# USB_To_TTL.net
KiCad netlist of a schematic drawn in Altium Designer
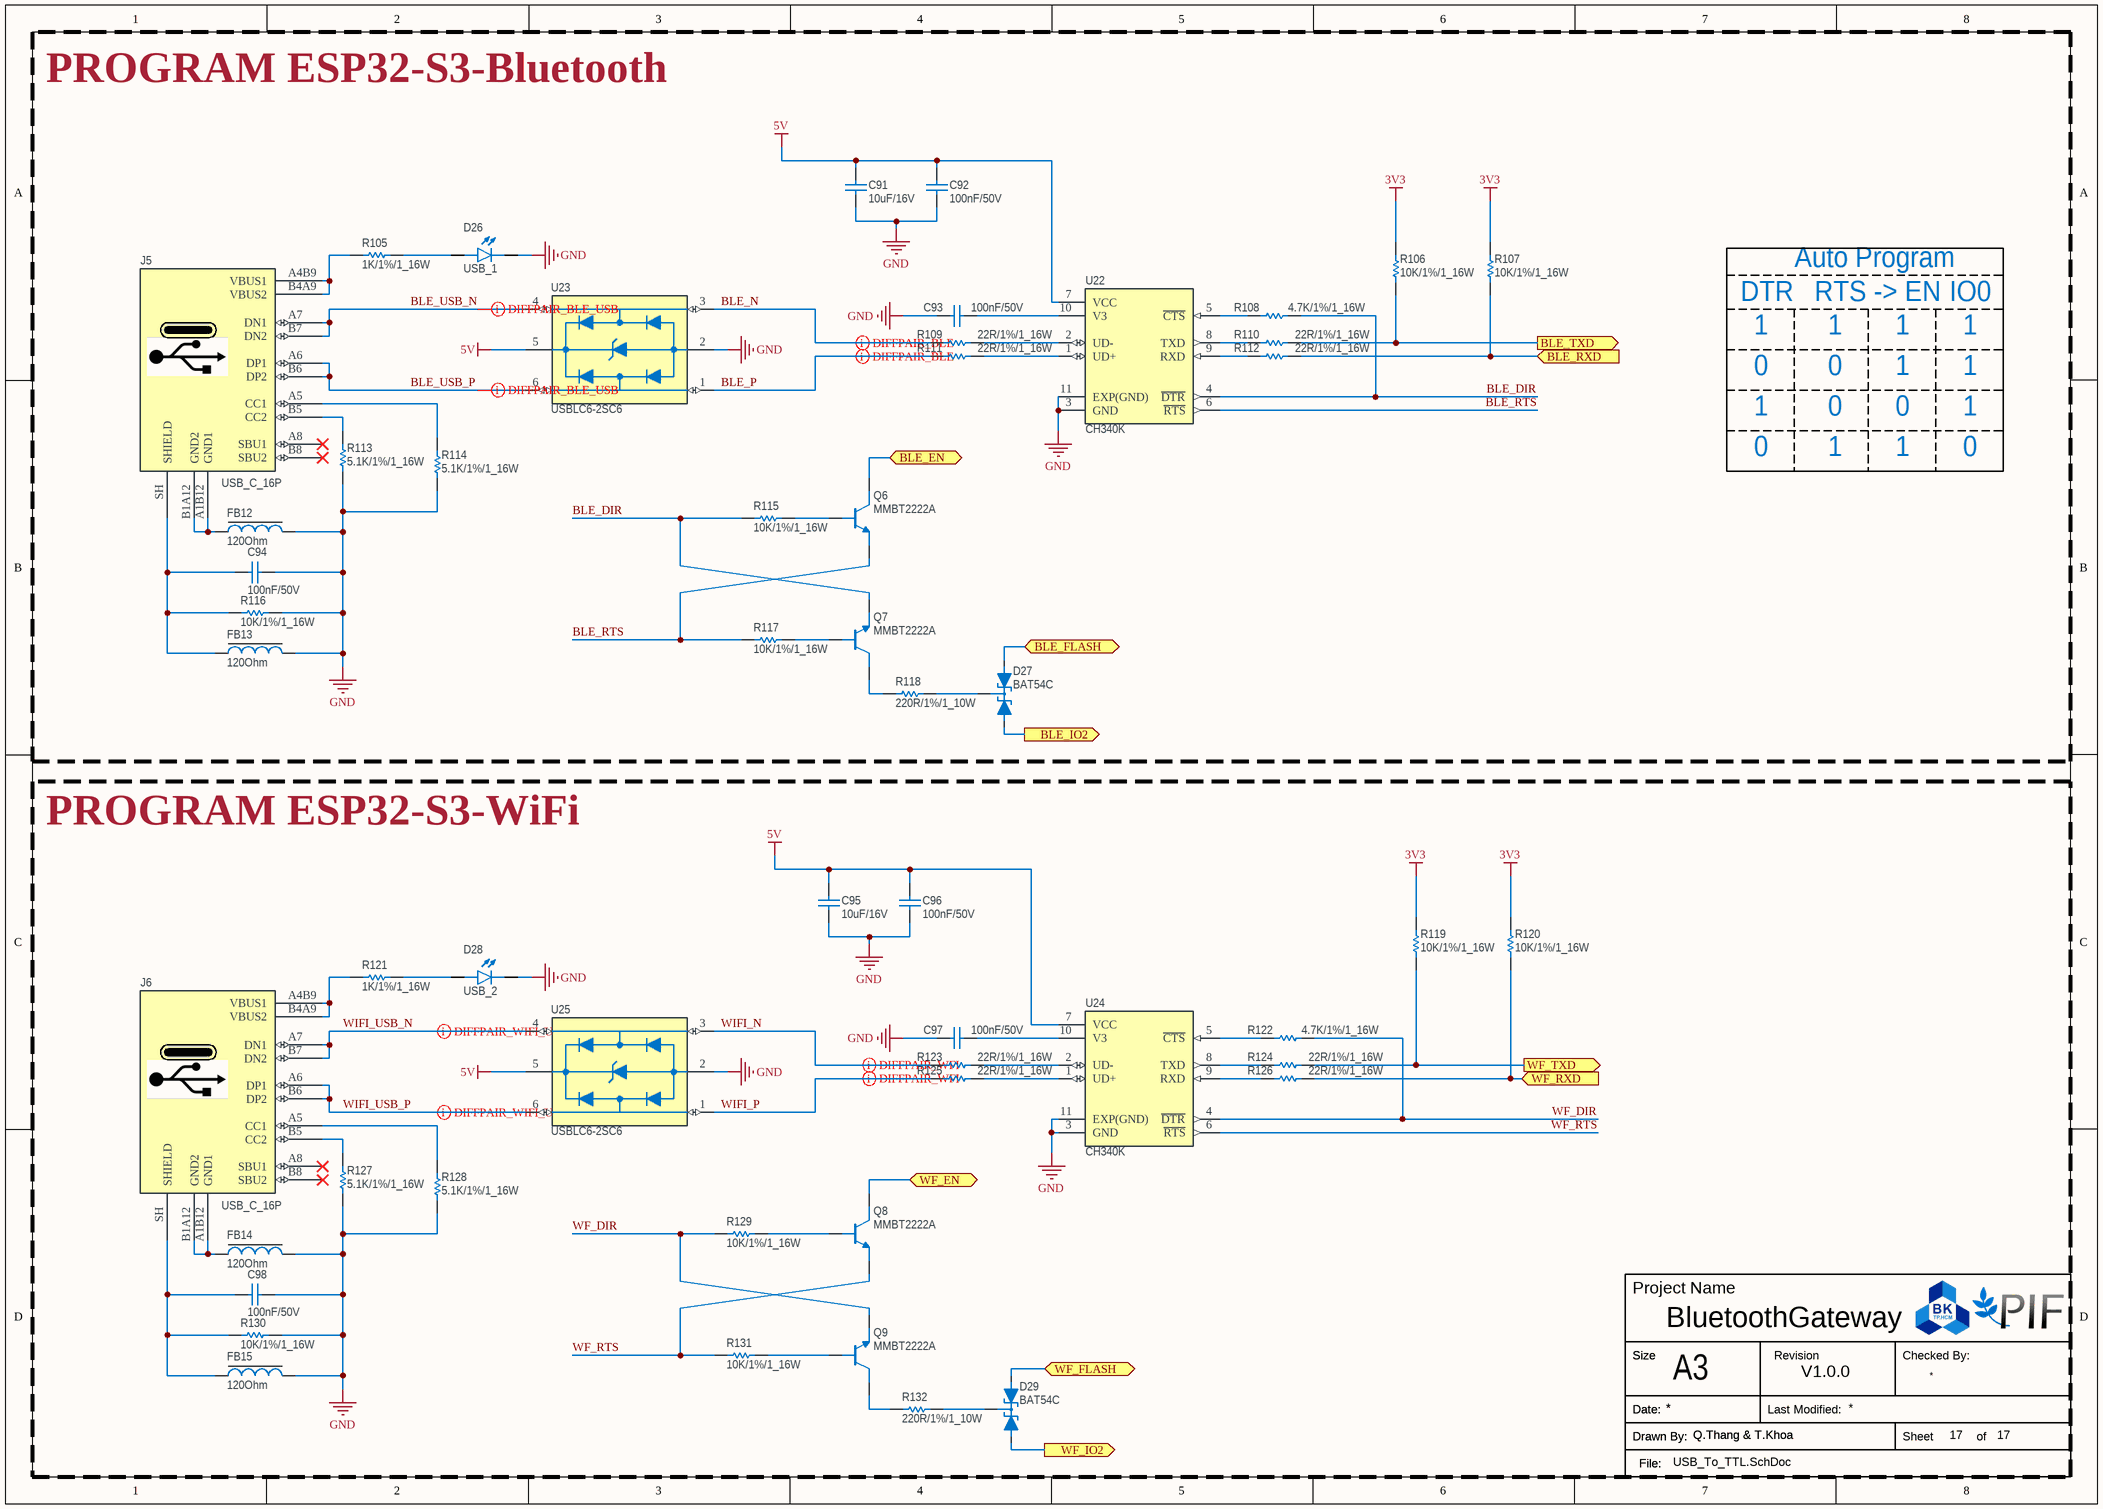
[diagram p0: USB_To_TTL.SchDoc]

(export (version "E")
  (design (tool "Eeschema 10.0.6"))
  (components
    (comp (ref "C91")
      (value "10uF/16V")
      (footprint "CAP_0603")
      (description "CAP, size 0603, 10uF, 16V")
      (fields (field (name "SUPPLY PART NUMBER") "Tụ Gốm 0603 10uF 16V"))
      (libsource (lib "BluetoothTracking") (part "Ceramic_Cap_10uF_16V_0603"))
    )
    (comp (ref "C92")
      (value "100nF/50V")
      (footprint "CAP_0603")
      (description "CAP, size 0603, 100nF, 50V")
      (fields (field (name "SUPPLY PART NUMBER") "Tụ Gốm 0603 100nF (0.1uF) 50V"))
      (libsource (lib "BluetoothTracking") (part "Ceramic_Cap_100nF_50V_0603"))
    )
    (comp (ref "C93")
      (value "100nF/50V")
      (footprint "CAP_0402")
      (description "CAP, size 0402, 100nF, 50V")
      (fields (field (name "SUPPLY PART NUMBER") "Tụ Gốm 0402 100nF (0.1uF) 50V"))
      (libsource (lib "BluetoothTracking") (part "Ceramic_Cap_100nF_50V_0402"))
    )
    (comp (ref "C94")
      (value "100nF/50V")
      (footprint "CAP_0402")
      (description "CAP, size 0402, 100nF, 50V")
      (fields (field (name "SUPPLY PART NUMBER") "Tụ Gốm 0402 100nF (0.1uF) 50V"))
      (libsource (lib "BluetoothTracking") (part "Ceramic_Cap_100nF_50V_0402"))
    )
    (comp (ref "C95")
      (value "10uF/16V")
      (footprint "CAP_0603")
      (description "CAP, size 0603, 10uF, 16V")
      (fields (field (name "SUPPLY PART NUMBER") "Tụ Gốm 0603 10uF 16V"))
      (libsource (lib "BluetoothTracking") (part "Ceramic_Cap_10uF_16V_0603"))
    )
    (comp (ref "C96")
      (value "100nF/50V")
      (footprint "CAP_0603")
      (description "CAP, size 0603, 100nF, 50V")
      (fields (field (name "SUPPLY PART NUMBER") "Tụ Gốm 0603 100nF (0.1uF) 50V"))
      (libsource (lib "BluetoothTracking") (part "Ceramic_Cap_100nF_50V_0603"))
    )
    (comp (ref "C97")
      (value "100nF/50V")
      (footprint "CAP_0402")
      (description "CAP, size 0402, 100nF, 50V")
      (fields (field (name "SUPPLY PART NUMBER") "Tụ Gốm 0402 100nF (0.1uF) 50V"))
      (libsource (lib "BluetoothTracking") (part "Ceramic_Cap_100nF_50V_0402"))
    )
    (comp (ref "C98")
      (value "100nF/50V")
      (footprint "CAP_0402")
      (description "CAP, size 0402, 100nF, 50V")
      (fields (field (name "SUPPLY PART NUMBER") "Tụ Gốm 0402 100nF (0.1uF) 50V"))
      (libsource (lib "BluetoothTracking") (part "Ceramic_Cap_100nF_50V_0402"))
    )
    (comp (ref "D26")
      (value "USB_1")
      (footprint "LED_0603Y")
      (description "LED Yellow 0603")
      (fields (field (name "SUPPLY PART NUMBER") "LED Vàng 0603 Dán SMD Trong Suốt Harvatek"))
      (libsource (lib "BluetoothTracking") (part "LED_Yellow_0603"))
    )
    (comp (ref "D27")
      (value "BAT54C")
      (footprint "SOT-23")
      (description "DIODE ARRAY SCHOTTKY 30V SOT23-3")
      (libsource (lib "BluetoothTracking") (part "BAT54C"))
    )
    (comp (ref "D28")
      (value "USB_2")
      (footprint "LED_0603Y")
      (description "LED Yellow 0603")
      (fields (field (name "SUPPLY PART NUMBER") "LED Vàng 0603 Dán SMD Trong Suốt Harvatek"))
      (libsource (lib "BluetoothTracking") (part "LED_Yellow_0603"))
    )
    (comp (ref "D29")
      (value "BAT54C")
      (footprint "SOT-23")
      (description "DIODE ARRAY SCHOTTKY 30V SOT23-3")
      (libsource (lib "BluetoothTracking") (part "BAT54C"))
    )
    (comp (ref "FB12")
      (value "120Ohm")
      (footprint "Ferrite_Bead_0805")
      (description "Ferrite Bead, size 0805, 120Ohm, 2A")
      (fields (field (name "SUPPLY PART NUMBER") "CBW201209U121T Ferrite Beads 2A 120 Ohm 0805"))
      (libsource (lib "BluetoothTracking") (part "Ferrite_Bead_120Ohm_2A_0805"))
    )
    (comp (ref "FB13")
      (value "120Ohm")
      (footprint "Ferrite_Bead_0805")
      (description "Ferrite Bead, size 0805, 120Ohm, 2A")
      (fields (field (name "SUPPLY PART NUMBER") "CBW201209U121T Ferrite Beads 2A 120 Ohm 0805"))
      (libsource (lib "BluetoothTracking") (part "Ferrite_Bead_120Ohm_2A_0805"))
    )
    (comp (ref "FB14")
      (value "120Ohm")
      (footprint "Ferrite_Bead_0805")
      (description "Ferrite Bead, size 0805, 120Ohm, 2A")
      (fields (field (name "SUPPLY PART NUMBER") "CBW201209U121T Ferrite Beads 2A 120 Ohm 0805"))
      (libsource (lib "BluetoothTracking") (part "Ferrite_Bead_120Ohm_2A_0805"))
    )
    (comp (ref "FB15")
      (value "120Ohm")
      (footprint "Ferrite_Bead_0805")
      (description "Ferrite Bead, size 0805, 120Ohm, 2A")
      (fields (field (name "SUPPLY PART NUMBER") "CBW201209U121T Ferrite Beads 2A 120 Ohm 0805"))
      (libsource (lib "BluetoothTracking") (part "Ferrite_Bead_120Ohm_2A_0805"))
    )
    (comp (ref "J5")
      (value "USB_C_16P")
      (footprint "USB_TypeC_3.1")
      (description "USB Type C - Connector, Top-mount SMT, 16pos ¦ Molex Incorporated 217179-0001")
      (fields (field (name "SUPPLY PART NUMBER") "Cổng USB Cái 3.1 Type C 16 Chân Thẳng Dán SMD"))
      (libsource (lib "BluetoothTracking") (part "USB_TypeC_3.1"))
    )
    (comp (ref "J6")
      (value "USB_C_16P")
      (footprint "USB_TypeC_3.1")
      (description "USB Type C - Connector, Top-mount SMT, 16pos ¦ Molex Incorporated 217179-0001")
      (fields (field (name "SUPPLY PART NUMBER") "Cổng USB Cái 3.1 Type C 16 Chân Thẳng Dán SMD"))
      (libsource (lib "BluetoothTracking") (part "USB_TypeC_3.1"))
    )
    (comp (ref "Q6")
      (value "MMBT2222A")
      (footprint "SOT-23")
      (description "Điện áp Vce max: 40V, dòng Ic max: 0.6A, công suất: 0.3W")
      (fields (field (name "SUPPLY PART NUMBER") "MMBT2222A 1P Transistor NPN 40V 0.6A 3 Chân SOT-23"))
      (libsource (lib "BluetoothTracking") (part "MMBT2222A"))
    )
    (comp (ref "Q7")
      (value "MMBT2222A")
      (footprint "SOT-23")
      (description "Điện áp Vce max: 40V, dòng Ic max: 0.6A, công suất: 0.3W")
      (fields (field (name "SUPPLY PART NUMBER") "MMBT2222A 1P Transistor NPN 40V 0.6A 3 Chân SOT-23"))
      (libsource (lib "BluetoothTracking") (part "MMBT2222A"))
    )
    (comp (ref "Q8")
      (value "MMBT2222A")
      (footprint "SOT-23")
      (description "Điện áp Vce max: 40V, dòng Ic max: 0.6A, công suất: 0.3W")
      (fields (field (name "SUPPLY PART NUMBER") "MMBT2222A 1P Transistor NPN 40V 0.6A 3 Chân SOT-23"))
      (libsource (lib "BluetoothTracking") (part "MMBT2222A"))
    )
    (comp (ref "Q9")
      (value "MMBT2222A")
      (footprint "SOT-23")
      (description "Điện áp Vce max: 40V, dòng Ic max: 0.6A, công suất: 0.3W")
      (fields (field (name "SUPPLY PART NUMBER") "MMBT2222A 1P Transistor NPN 40V 0.6A 3 Chân SOT-23"))
      (libsource (lib "BluetoothTracking") (part "MMBT2222A"))
    )
    (comp (ref "R105")
      (value "1K/1%/1_16W")
      (footprint "RESISTOR_0402")
      (description "Resistor 0402 1KOhm 1% 1_16W")
      (fields (field (name "SUPPLY PART NUMBER") "Điện Trở 1 KOhm 0402 1%"))
      (libsource (lib "BluetoothTracking") (part "Res_1K_0402_1%"))
    )
    (comp (ref "R106")
      (value "10K/1%/1_16W")
      (footprint "RESISTOR_0402")
      (description "Resistor 0402 10KOhm 1% 1_16W")
      (fields (field (name "SUPPLY PART NUMBER") "Điện Trở 10 KOhm 0402 1%"))
      (libsource (lib "BluetoothTracking") (part "Res_10K_0402_1%"))
    )
    (comp (ref "R107")
      (value "10K/1%/1_16W")
      (footprint "RESISTOR_0402")
      (description "Resistor 0402 10KOhm 1% 1_16W")
      (fields (field (name "SUPPLY PART NUMBER") "Điện Trở 10 KOhm 0402 1%"))
      (libsource (lib "BluetoothTracking") (part "Res_10K_0402_1%"))
    )
    (comp (ref "R108")
      (value "4.7K/1%/1_16W")
      (footprint "RESISTOR_0402")
      (description "Resistor 0402 4.7KOhm 1% 1_16W")
      (fields (field (name "SUPPLY PART NUMBER") "Điện Trở 4.7 KOhm 0402 1%"))
      (libsource (lib "BluetoothTracking") (part "Res_4.7K_0402_1%"))
    )
    (comp (ref "R109")
      (value "22R/1%/1_16W")
      (footprint "RESISTOR_0402")
      (description "Resistor 0402 22 Ohm 1% 1_16W")
      (libsource (lib "BluetoothTracking") (part "Res_22R_0402_1%"))
    )
    (comp (ref "R110")
      (value "22R/1%/1_16W")
      (footprint "RESISTOR_0402")
      (description "Resistor 0402 22 Ohm 1% 1_16W")
      (libsource (lib "BluetoothTracking") (part "Res_22R_0402_1%"))
    )
    (comp (ref "R111")
      (value "22R/1%/1_16W")
      (footprint "RESISTOR_0402")
      (description "Resistor 0402 22 Ohm 1% 1_16W")
      (libsource (lib "BluetoothTracking") (part "Res_22R_0402_1%"))
    )
    (comp (ref "R112")
      (value "22R/1%/1_16W")
      (footprint "RESISTOR_0402")
      (description "Resistor 0402 22 Ohm 1% 1_16W")
      (libsource (lib "BluetoothTracking") (part "Res_22R_0402_1%"))
    )
    (comp (ref "R113")
      (value "5.1K/1%/1_16W")
      (footprint "RESISTOR_0402")
      (description "Resistor 0402 5.1KOhm 1% 1_16W")
      (libsource (lib "BluetoothTracking") (part "Res_5.1K_0402_1%"))
    )
    (comp (ref "R114")
      (value "5.1K/1%/1_16W")
      (footprint "RESISTOR_0402")
      (description "Resistor 0402 5.1KOhm 1% 1_16W")
      (libsource (lib "BluetoothTracking") (part "Res_5.1K_0402_1%"))
    )
    (comp (ref "R115")
      (value "10K/1%/1_16W")
      (footprint "RESISTOR_0402")
      (description "Resistor 0402 10KOhm 1% 1_16W")
      (fields (field (name "SUPPLY PART NUMBER") "Điện Trở 10 KOhm 0402 1%"))
      (libsource (lib "BluetoothTracking") (part "Res_10K_0402_1%"))
    )
    (comp (ref "R116")
      (value "10K/1%/1_16W")
      (footprint "RESISTOR_0402")
      (description "Resistor 0402 10KOhm 1% 1_16W")
      (fields (field (name "SUPPLY PART NUMBER") "Điện Trở 10 KOhm 0402 1%"))
      (libsource (lib "BluetoothTracking") (part "Res_10K_0402_1%"))
    )
    (comp (ref "R117")
      (value "10K/1%/1_16W")
      (footprint "RESISTOR_0402")
      (description "Resistor 0402 10KOhm 1% 1_16W")
      (fields (field (name "SUPPLY PART NUMBER") "Điện Trở 10 KOhm 0402 1%"))
      (libsource (lib "BluetoothTracking") (part "Res_10K_0402_1%"))
    )
    (comp (ref "R118")
      (value "220R/1%/1_10W")
      (footprint "Resistor_0603")
      (description "Resistor 0603 220 Ohm 1% 1_10W")
      (fields (field (name "SUPPLY PART NUMBER") "Điện Trở 220 Ohm 0603 1%"))
      (libsource (lib "BluetoothTracking") (part "Res_220R_0603_1%"))
    )
    (comp (ref "R119")
      (value "10K/1%/1_16W")
      (footprint "RESISTOR_0402")
      (description "Resistor 0402 10KOhm 1% 1_16W")
      (fields (field (name "SUPPLY PART NUMBER") "Điện Trở 10 KOhm 0402 1%"))
      (libsource (lib "BluetoothTracking") (part "Res_10K_0402_1%"))
    )
    (comp (ref "R120")
      (value "10K/1%/1_16W")
      (footprint "RESISTOR_0402")
      (description "Resistor 0402 10KOhm 1% 1_16W")
      (fields (field (name "SUPPLY PART NUMBER") "Điện Trở 10 KOhm 0402 1%"))
      (libsource (lib "BluetoothTracking") (part "Res_10K_0402_1%"))
    )
    (comp (ref "R121")
      (value "1K/1%/1_16W")
      (footprint "RESISTOR_0402")
      (description "Resistor 0402 1KOhm 1% 1_16W")
      (fields (field (name "SUPPLY PART NUMBER") "Điện Trở 1 KOhm 0402 1%"))
      (libsource (lib "BluetoothTracking") (part "Res_1K_0402_1%"))
    )
    (comp (ref "R122")
      (value "4.7K/1%/1_16W")
      (footprint "RESISTOR_0402")
      (description "Resistor 0402 4.7KOhm 1% 1_16W")
      (fields (field (name "SUPPLY PART NUMBER") "Điện Trở 4.7 KOhm 0402 1%"))
      (libsource (lib "BluetoothTracking") (part "Res_4.7K_0402_1%"))
    )
    (comp (ref "R123")
      (value "22R/1%/1_16W")
      (footprint "RESISTOR_0402")
      (description "Resistor 0402 22 Ohm 1% 1_16W")
      (libsource (lib "BluetoothTracking") (part "Res_22R_0402_1%"))
    )
    (comp (ref "R124")
      (value "22R/1%/1_16W")
      (footprint "RESISTOR_0402")
      (description "Resistor 0402 22 Ohm 1% 1_16W")
      (libsource (lib "BluetoothTracking") (part "Res_22R_0402_1%"))
    )
    (comp (ref "R125")
      (value "22R/1%/1_16W")
      (footprint "RESISTOR_0402")
      (description "Resistor 0402 22 Ohm 1% 1_16W")
      (libsource (lib "BluetoothTracking") (part "Res_22R_0402_1%"))
    )
    (comp (ref "R126")
      (value "22R/1%/1_16W")
      (footprint "RESISTOR_0402")
      (description "Resistor 0402 22 Ohm 1% 1_16W")
      (libsource (lib "BluetoothTracking") (part "Res_22R_0402_1%"))
    )
    (comp (ref "R127")
      (value "5.1K/1%/1_16W")
      (footprint "RESISTOR_0402")
      (description "Resistor 0402 5.1KOhm 1% 1_16W")
      (libsource (lib "BluetoothTracking") (part "Res_5.1K_0402_1%"))
    )
    (comp (ref "R128")
      (value "5.1K/1%/1_16W")
      (footprint "RESISTOR_0402")
      (description "Resistor 0402 5.1KOhm 1% 1_16W")
      (libsource (lib "BluetoothTracking") (part "Res_5.1K_0402_1%"))
    )
    (comp (ref "R129")
      (value "10K/1%/1_16W")
      (footprint "RESISTOR_0402")
      (description "Resistor 0402 10KOhm 1% 1_16W")
      (fields (field (name "SUPPLY PART NUMBER") "Điện Trở 10 KOhm 0402 1%"))
      (libsource (lib "BluetoothTracking") (part "Res_10K_0402_1%"))
    )
    (comp (ref "R130")
      (value "10K/1%/1_16W")
      (footprint "RESISTOR_0402")
      (description "Resistor 0402 10KOhm 1% 1_16W")
      (fields (field (name "SUPPLY PART NUMBER") "Điện Trở 10 KOhm 0402 1%"))
      (libsource (lib "BluetoothTracking") (part "Res_10K_0402_1%"))
    )
    (comp (ref "R131")
      (value "10K/1%/1_16W")
      (footprint "RESISTOR_0402")
      (description "Resistor 0402 10KOhm 1% 1_16W")
      (fields (field (name "SUPPLY PART NUMBER") "Điện Trở 10 KOhm 0402 1%"))
      (libsource (lib "BluetoothTracking") (part "Res_10K_0402_1%"))
    )
    (comp (ref "R132")
      (value "220R/1%/1_10W")
      (footprint "Resistor_0603")
      (description "Resistor 0603 220 Ohm 1% 1_10W")
      (fields (field (name "SUPPLY PART NUMBER") "Điện Trở 220 Ohm 0603 1%"))
      (libsource (lib "BluetoothTracking") (part "Res_220R_0603_1%"))
    )
    (comp (ref "U22")
      (value "CH340K")
      (footprint "EESOP10")
      (description "USB to Serial Port Chip")
      (libsource (lib "BluetoothTracking") (part "CH340K"))
    )
    (comp (ref "U23")
      (value "USBLC6-2SC6")
      (footprint "SOT-23-6")
      (description "17V Clamp 5A (8/20Âµs) Ipp Tvs Diode Surface Mount SOT-23-6")
      (fields (field (name "SUPPLY PART NUMBER") "USBLC6-2SC6 TVS diode 5.25V 17V SOT23-6"))
      (libsource (lib "BluetoothTracking") (part "USBLC6-2SC6"))
    )
    (comp (ref "U24")
      (value "CH340K")
      (footprint "EESOP10")
      (description "USB to Serial Port Chip")
      (libsource (lib "BluetoothTracking") (part "CH340K"))
    )
    (comp (ref "U25")
      (value "USBLC6-2SC6")
      (footprint "SOT-23-6")
      (description "17V Clamp 5A (8/20Âµs) Ipp Tvs Diode Surface Mount SOT-23-6")
      (fields (field (name "SUPPLY PART NUMBER") "USBLC6-2SC6 TVS diode 5.25V 17V SOT23-6"))
      (libsource (lib "BluetoothTracking") (part "USBLC6-2SC6"))
    )
  )
  (nets
    (net (code "1") (name "/BLE_DIR") (class "Default")
      (node (ref "Q7") (pin "2") (pinfunction "E_2") (pintype "passive"))
      (node (ref "R108") (pin "2") (pinfunction "2_2") (pintype "passive"))
      (node (ref "R115") (pin "1") (pinfunction "1_1") (pintype "passive"))
      (node (ref "U22") (pin "4") (pinfunction "~{DTR}_4") (pintype "output"))
    )
    (net (code "2") (name "/BLE_EN") (class "Default")
      (node (ref "Q6") (pin "3") (pinfunction "C_3") (pintype "passive"))
    )
    (net (code "3") (name "/BLE_FLASH") (class "Default")
      (node (ref "D27") (pin "2") (pinfunction "A2_2") (pintype "passive"))
    )
    (net (code "4") (name "/BLE_IO2") (class "Default")
      (node (ref "D27") (pin "1") (pinfunction "A1_1") (pintype "passive"))
    )
    (net (code "5") (name "/BLE_N") (class "Default")
      (node (ref "R109") (pin "1") (pinfunction "1_1") (pintype "passive"))
      (node (ref "U23") (pin "3") (pinfunction "I/O2_IN_3") (pintype "bidirectional"))
    )
    (net (code "6") (name "/BLE_P") (class "Default")
      (node (ref "R111") (pin "1") (pinfunction "1_1") (pintype "passive"))
      (node (ref "U23") (pin "1") (pinfunction "I/O1_IN_1") (pintype "bidirectional"))
    )
    (net (code "7") (name "/BLE_RTS") (class "Default")
      (node (ref "Q6") (pin "2") (pinfunction "E_2") (pintype "passive"))
      (node (ref "R117") (pin "1") (pinfunction "1_1") (pintype "passive"))
      (node (ref "U22") (pin "6") (pinfunction "~{RTS}_6") (pintype "output"))
    )
    (net (code "8") (name "/BLE_RXD") (class "Default")
      (node (ref "R107") (pin "1") (pinfunction "1_1") (pintype "passive"))
      (node (ref "R112") (pin "2") (pinfunction "2_2") (pintype "passive"))
    )
    (net (code "9") (name "/BLE_TXD") (class "Default")
      (node (ref "R106") (pin "1") (pinfunction "1_1") (pintype "passive"))
      (node (ref "R110") (pin "2") (pinfunction "2_2") (pintype "passive"))
    )
    (net (code "10") (name "/BLE_USB_N") (class "Default")
      (node (ref "J5") (pin "A7") (pinfunction "DN1_A7") (pintype "bidirectional"))
      (node (ref "J5") (pin "B7") (pinfunction "DN2_B7") (pintype "bidirectional"))
      (node (ref "U23") (pin "4") (pinfunction "I/O2_OUT_4") (pintype "bidirectional"))
    )
    (net (code "11") (name "/BLE_USB_P") (class "Default")
      (node (ref "J5") (pin "A6") (pinfunction "DP1_A6") (pintype "bidirectional"))
      (node (ref "J5") (pin "B6") (pinfunction "DP2_B6") (pintype "bidirectional"))
      (node (ref "U23") (pin "6") (pinfunction "I/O1_OUT_6") (pintype "bidirectional"))
    )
    (net (code "12") (name "/WF_DIR") (class "Default")
      (node (ref "Q9") (pin "2") (pinfunction "E_2") (pintype "passive"))
      (node (ref "R122") (pin "2") (pinfunction "2_2") (pintype "passive"))
      (node (ref "R129") (pin "1") (pinfunction "1_1") (pintype "passive"))
      (node (ref "U24") (pin "4") (pinfunction "~{DTR}_4") (pintype "output"))
    )
    (net (code "13") (name "/WF_EN") (class "Default")
      (node (ref "Q8") (pin "3") (pinfunction "C_3") (pintype "passive"))
    )
    (net (code "14") (name "/WF_FLASH") (class "Default")
      (node (ref "D29") (pin "2") (pinfunction "A2_2") (pintype "passive"))
    )
    (net (code "15") (name "/WF_IO2") (class "Default")
      (node (ref "D29") (pin "1") (pinfunction "A1_1") (pintype "passive"))
    )
    (net (code "16") (name "/WF_RTS") (class "Default")
      (node (ref "Q8") (pin "2") (pinfunction "E_2") (pintype "passive"))
      (node (ref "R131") (pin "1") (pinfunction "1_1") (pintype "passive"))
      (node (ref "U24") (pin "6") (pinfunction "~{RTS}_6") (pintype "output"))
    )
    (net (code "17") (name "/WF_RXD") (class "Default")
      (node (ref "R120") (pin "1") (pinfunction "1_1") (pintype "passive"))
      (node (ref "R126") (pin "2") (pinfunction "2_2") (pintype "passive"))
    )
    (net (code "18") (name "/WF_TXD") (class "Default")
      (node (ref "R119") (pin "1") (pinfunction "1_1") (pintype "passive"))
      (node (ref "R124") (pin "2") (pinfunction "2_2") (pintype "passive"))
    )
    (net (code "19") (name "/WIFI_N") (class "Default")
      (node (ref "R123") (pin "1") (pinfunction "1_1") (pintype "passive"))
      (node (ref "U25") (pin "3") (pinfunction "I/O2_IN_3") (pintype "bidirectional"))
    )
    (net (code "20") (name "/WIFI_P") (class "Default")
      (node (ref "R125") (pin "1") (pinfunction "1_1") (pintype "passive"))
      (node (ref "U25") (pin "1") (pinfunction "I/O1_IN_1") (pintype "bidirectional"))
    )
    (net (code "21") (name "/WIFI_USB_N") (class "Default")
      (node (ref "J6") (pin "A7") (pinfunction "DN1_A7") (pintype "bidirectional"))
      (node (ref "J6") (pin "B7") (pinfunction "DN2_B7") (pintype "bidirectional"))
      (node (ref "U25") (pin "4") (pinfunction "I/O2_OUT_4") (pintype "bidirectional"))
    )
    (net (code "22") (name "/WIFI_USB_P") (class "Default")
      (node (ref "J6") (pin "A6") (pinfunction "DP1_A6") (pintype "bidirectional"))
      (node (ref "J6") (pin "B6") (pinfunction "DP2_B6") (pintype "bidirectional"))
      (node (ref "U25") (pin "6") (pinfunction "I/O1_OUT_6") (pintype "bidirectional"))
    )
    (net (code "23") (name "3V3") (class "Default")
      (node (ref "R106") (pin "2") (pinfunction "2_2") (pintype "passive"))
      (node (ref "R107") (pin "2") (pinfunction "2_2") (pintype "passive"))
      (node (ref "R119") (pin "2") (pinfunction "2_2") (pintype "passive"))
      (node (ref "R120") (pin "2") (pinfunction "2_2") (pintype "passive"))
    )
    (net (code "24") (name "5V") (class "Default")
      (node (ref "C91") (pin "2") (pinfunction "2_2") (pintype "passive"))
      (node (ref "C92") (pin "2") (pinfunction "2_2") (pintype "passive"))
      (node (ref "C95") (pin "2") (pinfunction "2_2") (pintype "passive"))
      (node (ref "C96") (pin "2") (pinfunction "2_2") (pintype "passive"))
      (node (ref "U22") (pin "7") (pinfunction "VCC_7") (pintype "power_in"))
      (node (ref "U23") (pin "5") (pinfunction "VBUS_5") (pintype "power_in"))
      (node (ref "U24") (pin "7") (pinfunction "VCC_7") (pintype "power_in"))
      (node (ref "U25") (pin "5") (pinfunction "VBUS_5") (pintype "power_in"))
    )
    (net (code "25") (name "GND") (class "Default")
      (node (ref "C91") (pin "1") (pinfunction "1_1") (pintype "passive"))
      (node (ref "C92") (pin "1") (pinfunction "1_1") (pintype "passive"))
      (node (ref "C93") (pin "1") (pinfunction "1_1") (pintype "passive"))
      (node (ref "C94") (pin "2") (pinfunction "2_2") (pintype "passive"))
      (node (ref "C95") (pin "1") (pinfunction "1_1") (pintype "passive"))
      (node (ref "C96") (pin "1") (pinfunction "1_1") (pintype "passive"))
      (node (ref "C97") (pin "1") (pinfunction "1_1") (pintype "passive"))
      (node (ref "C98") (pin "2") (pinfunction "2_2") (pintype "passive"))
      (node (ref "D26") (pin "C") (pinfunction "C_C") (pintype "passive"))
      (node (ref "D28") (pin "C") (pinfunction "C_C") (pintype "passive"))
      (node (ref "FB12") (pin "2") (pinfunction "2_2") (pintype "passive"))
      (node (ref "FB13") (pin "2") (pinfunction "2_2") (pintype "passive"))
      (node (ref "FB14") (pin "2") (pinfunction "2_2") (pintype "passive"))
      (node (ref "FB15") (pin "2") (pinfunction "2_2") (pintype "passive"))
      (node (ref "R113") (pin "1") (pinfunction "1_1") (pintype "passive"))
      (node (ref "R114") (pin "1") (pinfunction "1_1") (pintype "passive"))
      (node (ref "R116") (pin "2") (pinfunction "2_2") (pintype "passive"))
      (node (ref "R127") (pin "1") (pinfunction "1_1") (pintype "passive"))
      (node (ref "R128") (pin "1") (pinfunction "1_1") (pintype "passive"))
      (node (ref "R130") (pin "2") (pinfunction "2_2") (pintype "passive"))
      (node (ref "U22") (pin "11") (pinfunction "EXP(GND)_11") (pintype "power_in"))
      (node (ref "U22") (pin "3") (pinfunction "GND_3") (pintype "power_in"))
      (node (ref "U23") (pin "2") (pinfunction "GND_2") (pintype "power_in"))
      (node (ref "U24") (pin "11") (pinfunction "EXP(GND)_11") (pintype "power_in"))
      (node (ref "U24") (pin "3") (pinfunction "GND_3") (pintype "power_in"))
      (node (ref "U25") (pin "2") (pinfunction "GND_2") (pintype "power_in"))
    )
    (net (code "26") (name "Net-(D26-PadA)") (class "Default")
      (node (ref "D26") (pin "A") (pinfunction "A_A") (pintype "passive"))
      (node (ref "R105") (pin "2") (pinfunction "2_2") (pintype "passive"))
    )
    (net (code "27") (name "Net-(D27-C)") (class "Default")
      (node (ref "D27") (pin "3") (pinfunction "C_3") (pintype "passive"))
      (node (ref "R118") (pin "2") (pinfunction "2_2") (pintype "passive"))
    )
    (net (code "28") (name "Net-(D28-PadA)") (class "Default")
      (node (ref "D28") (pin "A") (pinfunction "A_A") (pintype "passive"))
      (node (ref "R121") (pin "2") (pinfunction "2_2") (pintype "passive"))
    )
    (net (code "29") (name "Net-(D29-C)") (class "Default")
      (node (ref "D29") (pin "3") (pinfunction "C_3") (pintype "passive"))
      (node (ref "R132") (pin "2") (pinfunction "2_2") (pintype "passive"))
    )
    (net (code "30") (name "Net-(J5-CC1)") (class "Default")
      (node (ref "J5") (pin "A5") (pinfunction "CC1_A5") (pintype "bidirectional"))
      (node (ref "R114") (pin "2") (pinfunction "2_2") (pintype "passive"))
    )
    (net (code "31") (name "Net-(J5-CC2)") (class "Default")
      (node (ref "J5") (pin "B5") (pinfunction "CC2_B5") (pintype "bidirectional"))
      (node (ref "R113") (pin "2") (pinfunction "2_2") (pintype "passive"))
    )
    (net (code "32") (name "Net-(J5-GND1)") (class "Default")
      (node (ref "FB12") (pin "1") (pinfunction "1_1") (pintype "passive"))
      (node (ref "J5") (pin "A1B12") (pinfunction "GND1_A1B12") (pintype "power_in"))
      (node (ref "J5") (pin "B1A12") (pinfunction "GND2_B1A12") (pintype "power_in"))
    )
    (net (code "33") (name "Net-(J5-SHIELD)") (class "Default")
      (node (ref "C94") (pin "1") (pinfunction "1_1") (pintype "passive"))
      (node (ref "FB13") (pin "1") (pinfunction "1_1") (pintype "passive"))
      (node (ref "J5") (pin "SH") (pinfunction "SHIELD_SH") (pintype "passive"))
      (node (ref "R116") (pin "1") (pinfunction "1_1") (pintype "passive"))
    )
    (net (code "34") (name "Net-(J5-VBUS1)") (class "Default")
      (node (ref "J5") (pin "A4B9") (pinfunction "VBUS1_A4B9") (pintype "power_in"))
      (node (ref "J5") (pin "B4A9") (pinfunction "VBUS2_B4A9") (pintype "power_in"))
      (node (ref "R105") (pin "1") (pinfunction "1_1") (pintype "passive"))
    )
    (net (code "35") (name "Net-(J6-CC1)") (class "Default")
      (node (ref "J6") (pin "A5") (pinfunction "CC1_A5") (pintype "bidirectional"))
      (node (ref "R128") (pin "2") (pinfunction "2_2") (pintype "passive"))
    )
    (net (code "36") (name "Net-(J6-CC2)") (class "Default")
      (node (ref "J6") (pin "B5") (pinfunction "CC2_B5") (pintype "bidirectional"))
      (node (ref "R127") (pin "2") (pinfunction "2_2") (pintype "passive"))
    )
    (net (code "37") (name "Net-(J6-GND1)") (class "Default")
      (node (ref "FB14") (pin "1") (pinfunction "1_1") (pintype "passive"))
      (node (ref "J6") (pin "A1B12") (pinfunction "GND1_A1B12") (pintype "power_in"))
      (node (ref "J6") (pin "B1A12") (pinfunction "GND2_B1A12") (pintype "power_in"))
    )
    (net (code "38") (name "Net-(J6-SHIELD)") (class "Default")
      (node (ref "C98") (pin "1") (pinfunction "1_1") (pintype "passive"))
      (node (ref "FB15") (pin "1") (pinfunction "1_1") (pintype "passive"))
      (node (ref "J6") (pin "SH") (pinfunction "SHIELD_SH") (pintype "passive"))
      (node (ref "R130") (pin "1") (pinfunction "1_1") (pintype "passive"))
    )
    (net (code "39") (name "Net-(J6-VBUS1)") (class "Default")
      (node (ref "J6") (pin "A4B9") (pinfunction "VBUS1_A4B9") (pintype "power_in"))
      (node (ref "J6") (pin "B4A9") (pinfunction "VBUS2_B4A9") (pintype "power_in"))
      (node (ref "R121") (pin "1") (pinfunction "1_1") (pintype "passive"))
    )
    (net (code "40") (name "Net-(Q6-B)") (class "Default")
      (node (ref "Q6") (pin "1") (pinfunction "B_1") (pintype "passive"))
      (node (ref "R115") (pin "2") (pinfunction "2_2") (pintype "passive"))
    )
    (net (code "41") (name "Net-(Q7-B)") (class "Default")
      (node (ref "Q7") (pin "1") (pinfunction "B_1") (pintype "passive"))
      (node (ref "R117") (pin "2") (pinfunction "2_2") (pintype "passive"))
    )
    (net (code "42") (name "Net-(Q7-C)") (class "Default")
      (node (ref "Q7") (pin "3") (pinfunction "C_3") (pintype "passive"))
      (node (ref "R118") (pin "1") (pinfunction "1_1") (pintype "passive"))
    )
    (net (code "43") (name "Net-(Q8-B)") (class "Default")
      (node (ref "Q8") (pin "1") (pinfunction "B_1") (pintype "passive"))
      (node (ref "R129") (pin "2") (pinfunction "2_2") (pintype "passive"))
    )
    (net (code "44") (name "Net-(Q9-B)") (class "Default")
      (node (ref "Q9") (pin "1") (pinfunction "B_1") (pintype "passive"))
      (node (ref "R131") (pin "2") (pinfunction "2_2") (pintype "passive"))
    )
    (net (code "45") (name "Net-(Q9-C)") (class "Default")
      (node (ref "Q9") (pin "3") (pinfunction "C_3") (pintype "passive"))
      (node (ref "R132") (pin "1") (pinfunction "1_1") (pintype "passive"))
    )
    (net (code "46") (name "Net-(U22-RXD)") (class "Default")
      (node (ref "R112") (pin "1") (pinfunction "1_1") (pintype "passive"))
      (node (ref "U22") (pin "9") (pinfunction "RXD_9") (pintype "input"))
    )
    (net (code "47") (name "Net-(U22-TXD)") (class "Default")
      (node (ref "R110") (pin "1") (pinfunction "1_1") (pintype "passive"))
      (node (ref "U22") (pin "8") (pinfunction "TXD_8") (pintype "output"))
    )
    (net (code "48") (name "Net-(U22-UD+)") (class "Default")
      (node (ref "R111") (pin "2") (pinfunction "2_2") (pintype "passive"))
      (node (ref "U22") (pin "1") (pinfunction "UD+_1") (pintype "bidirectional"))
    )
    (net (code "49") (name "Net-(U22-UD-)") (class "Default")
      (node (ref "R109") (pin "2") (pinfunction "2_2") (pintype "passive"))
      (node (ref "U22") (pin "2") (pinfunction "UD-_2") (pintype "bidirectional"))
    )
    (net (code "50") (name "Net-(U22-V3)") (class "Default")
      (node (ref "C93") (pin "2") (pinfunction "2_2") (pintype "passive"))
      (node (ref "U22") (pin "10") (pinfunction "V3_10") (pintype "power_in"))
    )
    (net (code "51") (name "Net-(U22-~{CTS})") (class "Default")
      (node (ref "R108") (pin "1") (pinfunction "1_1") (pintype "passive"))
      (node (ref "U22") (pin "5") (pinfunction "~{CTS}_5") (pintype "input"))
    )
    (net (code "52") (name "Net-(U24-RXD)") (class "Default")
      (node (ref "R126") (pin "1") (pinfunction "1_1") (pintype "passive"))
      (node (ref "U24") (pin "9") (pinfunction "RXD_9") (pintype "input"))
    )
    (net (code "53") (name "Net-(U24-TXD)") (class "Default")
      (node (ref "R124") (pin "1") (pinfunction "1_1") (pintype "passive"))
      (node (ref "U24") (pin "8") (pinfunction "TXD_8") (pintype "output"))
    )
    (net (code "54") (name "Net-(U24-UD+)") (class "Default")
      (node (ref "R125") (pin "2") (pinfunction "2_2") (pintype "passive"))
      (node (ref "U24") (pin "1") (pinfunction "UD+_1") (pintype "bidirectional"))
    )
    (net (code "55") (name "Net-(U24-UD-)") (class "Default")
      (node (ref "R123") (pin "2") (pinfunction "2_2") (pintype "passive"))
      (node (ref "U24") (pin "2") (pinfunction "UD-_2") (pintype "bidirectional"))
    )
    (net (code "56") (name "Net-(U24-V3)") (class "Default")
      (node (ref "C97") (pin "2") (pinfunction "2_2") (pintype "passive"))
      (node (ref "U24") (pin "10") (pinfunction "V3_10") (pintype "power_in"))
    )
    (net (code "57") (name "Net-(U24-~{CTS})") (class "Default")
      (node (ref "R122") (pin "1") (pinfunction "1_1") (pintype "passive"))
      (node (ref "U24") (pin "5") (pinfunction "~{CTS}_5") (pintype "input"))
    )
    (net (code "58") (name "unconnected-(J5-SBU1-PadA8)") (class "Default")
      (node (ref "J5") (pin "A8") (pinfunction "SBU1_A8") (pintype "bidirectional+no_connect"))
    )
    (net (code "59") (name "unconnected-(J5-SBU2-PadB8)") (class "Default")
      (node (ref "J5") (pin "B8") (pinfunction "SBU2_B8") (pintype "bidirectional+no_connect"))
    )
    (net (code "60") (name "unconnected-(J6-SBU1-PadA8)") (class "Default")
      (node (ref "J6") (pin "A8") (pinfunction "SBU1_A8") (pintype "bidirectional+no_connect"))
    )
    (net (code "61") (name "unconnected-(J6-SBU2-PadB8)") (class "Default")
      (node (ref "J6") (pin "B8") (pinfunction "SBU2_B8") (pintype "bidirectional+no_connect"))
    )
  )
)
